# LightLinkV2.net
KiCad netlist of a schematic drawn in Altium Designer
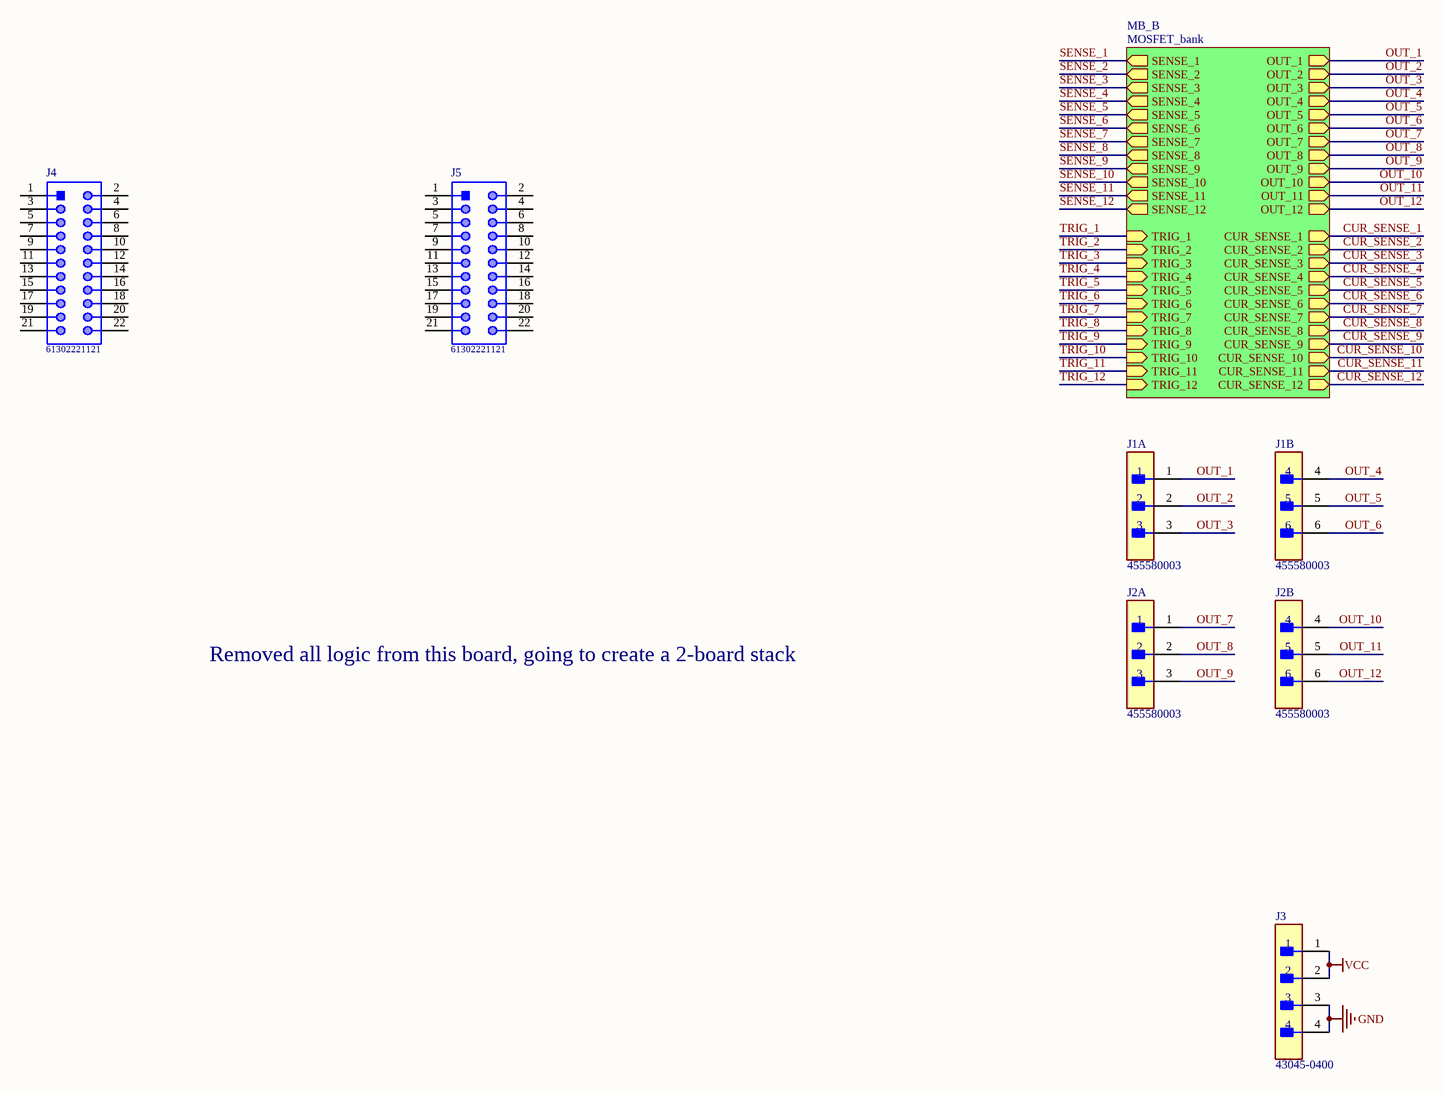
[diagram p0: LightLinkV2.SchDoc]

(export (version "E")
  (design (tool "Eeschema 10.0.6"))
  (components
    (comp (ref "J1")
      (value "455580003")
      (footprint "FP-455580003-MFG")
      (description "CONN HEADER R/A 6POS 4.2MM")
      (fields
        (field (name "OCTOPART") "https://octopart.com/45558-0003-molex-7672845")
        (field (name "MANUFACTURER") "Molex")
      )
      (libsource (lib "Altium Content Vault") (part "bb9cbdb24149a20ba329b4e86909569"))
    )
    (comp (ref "J2")
      (value "455580003")
      (footprint "FP-455580003-MFG")
      (description "CONN HEADER R/A 6POS 4.2MM")
      (fields
        (field (name "OCTOPART") "https://octopart.com/45558-0003-molex-7672845")
        (field (name "MANUFACTURER") "Molex")
      )
      (libsource (lib "Altium Content Vault") (part "bb9cbdb24149a20ba329b4e86909569"))
    )
    (comp (ref "J3")
      (value "43045-0400")
      (footprint "FP-43045-0400-MFG")
      (description "CONN HEADER R/A 4POS 3MM")
      (fields
        (field (name "MANUFACTURER") "Molex")
        (field (name "OCTOPART") "https://octopart.com/43045-0400-molex-287063")
      )
      (libsource (lib "Altium Content Vault") (part "c01754ab0efc13afb7424b896f394ef"))
    )
    (comp (ref "J4")
      (value "61302221121")
      (footprint "61302221121")
      (description "THT Vertical Pin Header WR-PHD, Pitch 2.54 mm, Dual Row, 22 pins")
      (fields (field (name "MANUFACTURER") "Wurth Elektronik") (field (name "PUBLISHER") "WurthElektronik"))
      (libsource (lib "Altium Content Vault") (part "WE-CN-2P-M-R22"))
    )
    (comp (ref "J5")
      (value "61302221121")
      (footprint "61302221121")
      (description "THT Vertical Pin Header WR-PHD, Pitch 2.54 mm, Dual Row, 22 pins")
      (fields (field (name "MANUFACTURER") "Wurth Elektronik") (field (name "PUBLISHER") "WurthElektronik"))
      (libsource (lib "Altium Content Vault") (part "WE-CN-2P-M-R22"))
    )
  )
  (nets
    (net (code "13") (name "/OUT_1") (class "Default")
      (node (ref "J1") (pin "1") (pinfunction "1_1") (pintype "passive"))
    )
    (net (code "14") (name "/OUT_2") (class "Default")
      (node (ref "J1") (pin "2") (pinfunction "2_2") (pintype "passive"))
    )
    (net (code "15") (name "/OUT_3") (class "Default")
      (node (ref "J1") (pin "3") (pinfunction "3_3") (pintype "passive"))
    )
    (net (code "16") (name "/OUT_4") (class "Default")
      (node (ref "J1") (pin "4") (pinfunction "4_4") (pintype "passive"))
    )
    (net (code "17") (name "/OUT_5") (class "Default")
      (node (ref "J1") (pin "5") (pinfunction "5_5") (pintype "passive"))
    )
    (net (code "18") (name "/OUT_6") (class "Default")
      (node (ref "J1") (pin "6") (pinfunction "6_6") (pintype "passive"))
    )
    (net (code "19") (name "/OUT_7") (class "Default")
      (node (ref "J2") (pin "1") (pinfunction "1_1") (pintype "passive"))
    )
    (net (code "20") (name "/OUT_8") (class "Default")
      (node (ref "J2") (pin "2") (pinfunction "2_2") (pintype "passive"))
    )
    (net (code "21") (name "/OUT_9") (class "Default")
      (node (ref "J2") (pin "3") (pinfunction "3_3") (pintype "passive"))
    )
    (net (code "22") (name "/OUT_10") (class "Default")
      (node (ref "J2") (pin "4") (pinfunction "4_4") (pintype "passive"))
    )
    (net (code "23") (name "/OUT_11") (class "Default")
      (node (ref "J2") (pin "5") (pinfunction "5_5") (pintype "passive"))
    )
    (net (code "24") (name "/OUT_12") (class "Default")
      (node (ref "J2") (pin "6") (pinfunction "6_6") (pintype "passive"))
    )
    (net (code "49") (name "GND") (class "Default")
      (node (ref "J3") (pin "3") (pinfunction "3_3") (pintype "passive"))
      (node (ref "J3") (pin "4") (pinfunction "4_4") (pintype "passive"))
    )
    (net (code "50") (name "VCC") (class "Default")
      (node (ref "J3") (pin "1") (pinfunction "1_1") (pintype "passive"))
      (node (ref "J3") (pin "2") (pinfunction "2_2") (pintype "passive"))
    )
    (net (code "51") (name "unconnected-(J4-Pad1)") (class "Default")
      (node (ref "J4") (pin "1") (pinfunction "1_1") (pintype "passive"))
    )
    (net (code "52") (name "unconnected-(J4-Pad2)") (class "Default")
      (node (ref "J4") (pin "2") (pinfunction "2_2") (pintype "passive"))
    )
    (net (code "53") (name "unconnected-(J4-Pad3)") (class "Default")
      (node (ref "J4") (pin "3") (pinfunction "3_3") (pintype "passive"))
    )
    (net (code "54") (name "unconnected-(J4-Pad4)") (class "Default")
      (node (ref "J4") (pin "4") (pinfunction "4_4") (pintype "passive"))
    )
    (net (code "55") (name "unconnected-(J4-Pad5)") (class "Default")
      (node (ref "J4") (pin "5") (pinfunction "5_5") (pintype "passive"))
    )
    (net (code "56") (name "unconnected-(J4-Pad6)") (class "Default")
      (node (ref "J4") (pin "6") (pinfunction "6_6") (pintype "passive"))
    )
    (net (code "57") (name "unconnected-(J4-Pad7)") (class "Default")
      (node (ref "J4") (pin "7") (pinfunction "7_7") (pintype "passive"))
    )
    (net (code "58") (name "unconnected-(J4-Pad8)") (class "Default")
      (node (ref "J4") (pin "8") (pinfunction "8_8") (pintype "passive"))
    )
    (net (code "59") (name "unconnected-(J4-Pad9)") (class "Default")
      (node (ref "J4") (pin "9") (pinfunction "9_9") (pintype "passive"))
    )
    (net (code "60") (name "unconnected-(J4-Pad10)") (class "Default")
      (node (ref "J4") (pin "10") (pinfunction "10_10") (pintype "passive"))
    )
    (net (code "61") (name "unconnected-(J4-Pad11)") (class "Default")
      (node (ref "J4") (pin "11") (pinfunction "11_11") (pintype "passive"))
    )
    (net (code "62") (name "unconnected-(J4-Pad12)") (class "Default")
      (node (ref "J4") (pin "12") (pinfunction "12_12") (pintype "passive"))
    )
    (net (code "63") (name "unconnected-(J4-Pad13)") (class "Default")
      (node (ref "J4") (pin "13") (pinfunction "13_13") (pintype "passive"))
    )
    (net (code "64") (name "unconnected-(J4-Pad14)") (class "Default")
      (node (ref "J4") (pin "14") (pinfunction "14_14") (pintype "passive"))
    )
    (net (code "65") (name "unconnected-(J4-Pad15)") (class "Default")
      (node (ref "J4") (pin "15") (pinfunction "15_15") (pintype "passive"))
    )
    (net (code "66") (name "unconnected-(J4-Pad16)") (class "Default")
      (node (ref "J4") (pin "16") (pinfunction "16_16") (pintype "passive"))
    )
    (net (code "67") (name "unconnected-(J4-Pad17)") (class "Default")
      (node (ref "J4") (pin "17") (pinfunction "17_17") (pintype "passive"))
    )
    (net (code "68") (name "unconnected-(J4-Pad18)") (class "Default")
      (node (ref "J4") (pin "18") (pinfunction "18_18") (pintype "passive"))
    )
    (net (code "69") (name "unconnected-(J4-Pad19)") (class "Default")
      (node (ref "J4") (pin "19") (pinfunction "19_19") (pintype "passive"))
    )
    (net (code "70") (name "unconnected-(J4-Pad20)") (class "Default")
      (node (ref "J4") (pin "20") (pinfunction "20_20") (pintype "passive"))
    )
    (net (code "71") (name "unconnected-(J4-Pad21)") (class "Default")
      (node (ref "J4") (pin "21") (pinfunction "21_21") (pintype "passive"))
    )
    (net (code "72") (name "unconnected-(J4-Pad22)") (class "Default")
      (node (ref "J4") (pin "22") (pinfunction "22_22") (pintype "passive"))
    )
    (net (code "73") (name "unconnected-(J5-Pad1)") (class "Default")
      (node (ref "J5") (pin "1") (pinfunction "1_1") (pintype "passive"))
    )
    (net (code "74") (name "unconnected-(J5-Pad2)") (class "Default")
      (node (ref "J5") (pin "2") (pinfunction "2_2") (pintype "passive"))
    )
    (net (code "75") (name "unconnected-(J5-Pad3)") (class "Default")
      (node (ref "J5") (pin "3") (pinfunction "3_3") (pintype "passive"))
    )
    (net (code "76") (name "unconnected-(J5-Pad4)") (class "Default")
      (node (ref "J5") (pin "4") (pinfunction "4_4") (pintype "passive"))
    )
    (net (code "77") (name "unconnected-(J5-Pad5)") (class "Default")
      (node (ref "J5") (pin "5") (pinfunction "5_5") (pintype "passive"))
    )
    (net (code "78") (name "unconnected-(J5-Pad6)") (class "Default")
      (node (ref "J5") (pin "6") (pinfunction "6_6") (pintype "passive"))
    )
    (net (code "79") (name "unconnected-(J5-Pad7)") (class "Default")
      (node (ref "J5") (pin "7") (pinfunction "7_7") (pintype "passive"))
    )
    (net (code "80") (name "unconnected-(J5-Pad8)") (class "Default")
      (node (ref "J5") (pin "8") (pinfunction "8_8") (pintype "passive"))
    )
    (net (code "81") (name "unconnected-(J5-Pad9)") (class "Default")
      (node (ref "J5") (pin "9") (pinfunction "9_9") (pintype "passive"))
    )
    (net (code "82") (name "unconnected-(J5-Pad10)") (class "Default")
      (node (ref "J5") (pin "10") (pinfunction "10_10") (pintype "passive"))
    )
    (net (code "83") (name "unconnected-(J5-Pad11)") (class "Default")
      (node (ref "J5") (pin "11") (pinfunction "11_11") (pintype "passive"))
    )
    (net (code "84") (name "unconnected-(J5-Pad12)") (class "Default")
      (node (ref "J5") (pin "12") (pinfunction "12_12") (pintype "passive"))
    )
    (net (code "85") (name "unconnected-(J5-Pad13)") (class "Default")
      (node (ref "J5") (pin "13") (pinfunction "13_13") (pintype "passive"))
    )
    (net (code "86") (name "unconnected-(J5-Pad14)") (class "Default")
      (node (ref "J5") (pin "14") (pinfunction "14_14") (pintype "passive"))
    )
    (net (code "87") (name "unconnected-(J5-Pad15)") (class "Default")
      (node (ref "J5") (pin "15") (pinfunction "15_15") (pintype "passive"))
    )
    (net (code "88") (name "unconnected-(J5-Pad16)") (class "Default")
      (node (ref "J5") (pin "16") (pinfunction "16_16") (pintype "passive"))
    )
    (net (code "89") (name "unconnected-(J5-Pad17)") (class "Default")
      (node (ref "J5") (pin "17") (pinfunction "17_17") (pintype "passive"))
    )
    (net (code "90") (name "unconnected-(J5-Pad18)") (class "Default")
      (node (ref "J5") (pin "18") (pinfunction "18_18") (pintype "passive"))
    )
    (net (code "91") (name "unconnected-(J5-Pad19)") (class "Default")
      (node (ref "J5") (pin "19") (pinfunction "19_19") (pintype "passive"))
    )
    (net (code "92") (name "unconnected-(J5-Pad20)") (class "Default")
      (node (ref "J5") (pin "20") (pinfunction "20_20") (pintype "passive"))
    )
    (net (code "93") (name "unconnected-(J5-Pad21)") (class "Default")
      (node (ref "J5") (pin "21") (pinfunction "21_21") (pintype "passive"))
    )
    (net (code "94") (name "unconnected-(J5-Pad22)") (class "Default")
      (node (ref "J5") (pin "22") (pinfunction "22_22") (pintype "passive"))
    )
  )
)
